# GSM_Relay.net
KiCad netlist of a schematic drawn in EAGLE
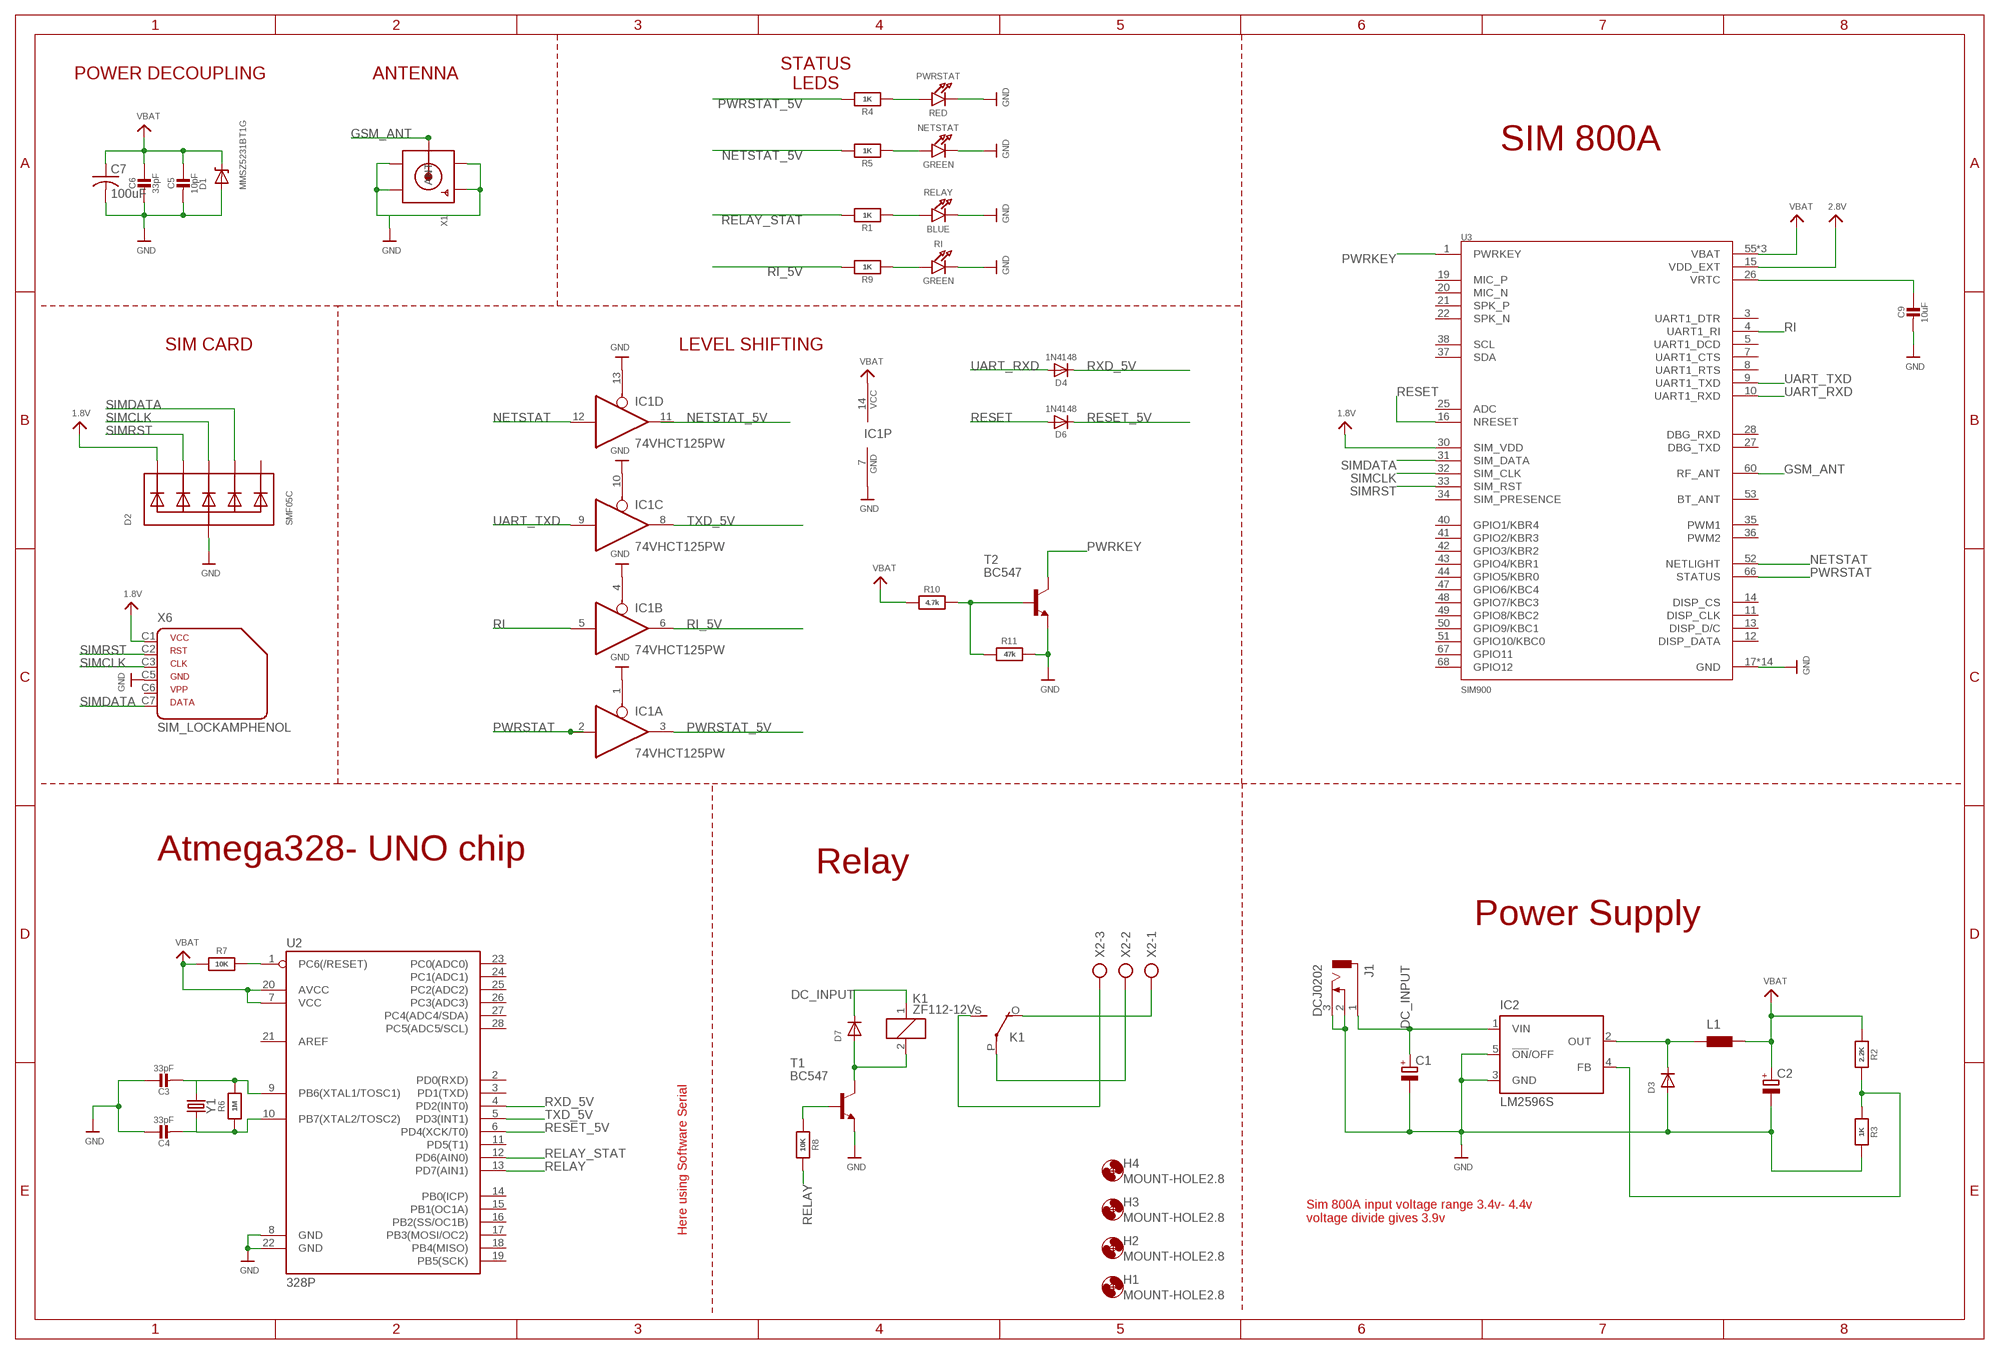
[diagram p0: schematic, sheet 1]

(export (version "E")
  (design (tool "Eeschema 10.0.6"))
  (components
    (comp (ref "C1")
      (value "CPOL-EUE")
      (footprint "eagle-import:PANASONIC_E")
      (libsource (lib "eagle-import") (part "CPOL-EUE"))
    )
    (comp (ref "C2")
      (value "CPOL-EUE")
      (footprint "eagle-import:PANASONIC_E")
      (libsource (lib "eagle-import") (part "CPOL-EUE"))
    )
    (comp (ref "C3")
      (value "33pF")
      (footprint "eagle-import:0805-NO")
      (libsource (lib "eagle-import") (part "CAP_CERAMIC0805-NOOUTLINE"))
    )
    (comp (ref "C4")
      (value "33pF")
      (footprint "eagle-import:0805-NO")
      (libsource (lib "eagle-import") (part "CAP_CERAMIC0805-NOOUTLINE"))
    )
    (comp (ref "C5")
      (value "10pF")
      (footprint "eagle-import:0805-NO")
      (libsource (lib "eagle-import") (part "CAP_CERAMIC0805-NOOUTLINE"))
    )
    (comp (ref "C6")
      (value "33pF")
      (footprint "eagle-import:0805-NO")
      (libsource (lib "eagle-import") (part "CAP_CERAMIC0805-NOOUTLINE"))
    )
    (comp (ref "C7")
      (value "100uF")
      (footprint "eagle-import:C1210")
      (libsource (lib "eagle-import") (part "C-USC1210"))
    )
    (comp (ref "C9")
      (value "10uF")
      (footprint "eagle-import:0805-NO")
      (libsource (lib "eagle-import") (part "CAP_CERAMIC0805-NOOUTLINE"))
    )
    (comp (ref "D1")
      (value "MMSZ5231BT1G")
      (footprint "eagle-import:SOD-123")
      (libsource (lib "eagle-import") (part "DIODE-ZENERSOD123"))
    )
    (comp (ref "D2")
      (value "SMF05C")
      (footprint "eagle-import:SOT363")
      (libsource (lib "eagle-import") (part "TVSARRAY_5LANE"))
    )
    (comp (ref "D3")
      (value "DIODESMA")
      (footprint "eagle-import:SMADIODE")
      (libsource (lib "eagle-import") (part "DIODESMA"))
    )
    (comp (ref "D4")
      (value "1N4148")
      (footprint "eagle-import:SOD-323")
      (libsource (lib "eagle-import") (part "DIODESOD-323"))
    )
    (comp (ref "D6")
      (value "1N4148")
      (footprint "eagle-import:SOD-323")
      (libsource (lib "eagle-import") (part "DIODESOD-323"))
    )
    (comp (ref "D7")
      (value "DIODESMA")
      (footprint "eagle-import:SMADIODE")
      (libsource (lib "eagle-import") (part "DIODESMA"))
    )
    (comp (ref "H1")
      (value "MOUNT-HOLE2.8")
      (footprint "eagle-import:2,8")
      (libsource (lib "eagle-import") (part "MOUNT-HOLE2.8"))
    )
    (comp (ref "H2")
      (value "MOUNT-HOLE2.8")
      (footprint "eagle-import:2,8")
      (libsource (lib "eagle-import") (part "MOUNT-HOLE2.8"))
    )
    (comp (ref "H3")
      (value "MOUNT-HOLE2.8")
      (footprint "eagle-import:2,8")
      (libsource (lib "eagle-import") (part "MOUNT-HOLE2.8"))
    )
    (comp (ref "H4")
      (value "MOUNT-HOLE2.8")
      (footprint "eagle-import:2,8")
      (libsource (lib "eagle-import") (part "MOUNT-HOLE2.8"))
    )
    (comp (ref "IC1")
      (value "74VHCT125PW")
      (footprint "eagle-import:TSSOP14")
      (libsource (lib "eagle-import") (part "74125PWABT"))
    )
    (comp (ref "IC2")
      (value "LM2596S")
      (footprint "eagle-import:TO263-5")
      (fields (field (name "MF") "NATIONAL SEMICONDUCTOR") (field (name "MPN") "LM2596S-ADJ/NOPB"))
      (libsource (lib "eagle-import") (part "LM2596S"))
    )
    (comp (ref "J1")
      (value "DCJ0202")
      (footprint "eagle-import:DCJ0202")
      (libsource (lib "eagle-import") (part "DCJ0202"))
    )
    (comp (ref "K1")
      (value "ZF112-12V")
      (footprint "eagle-import:ZF112")
      (libsource (lib "eagle-import") (part "ZF112"))
    )
    (comp (ref "L1")
      (value "PIS4720")
      (footprint "eagle-import:PIS4720")
      (libsource (lib "eagle-import") (part "PIS4720"))
    )
    (comp (ref "NETSTAT")
      (value "GREEN")
      (footprint "eagle-import:CHIPLED_0805_NOOUTLINE")
      (libsource (lib "eagle-import") (part "LED0805_NOOUTLINE"))
    )
    (comp (ref "PWRSTAT")
      (value "RED")
      (footprint "eagle-import:CHIPLED_0805_NOOUTLINE")
      (libsource (lib "eagle-import") (part "LED0805_NOOUTLINE"))
    )
    (comp (ref "R1")
      (value "1K")
      (footprint "eagle-import:0805-NO")
      (libsource (lib "eagle-import") (part "RESISTOR0805_NOOUTLINE"))
    )
    (comp (ref "R2")
      (value "2.2K")
      (footprint "eagle-import:0805-NO")
      (libsource (lib "eagle-import") (part "RESISTOR0805_NOOUTLINE"))
    )
    (comp (ref "R3")
      (value "1K")
      (footprint "eagle-import:0805-NO")
      (libsource (lib "eagle-import") (part "RESISTOR0805_NOOUTLINE"))
    )
    (comp (ref "R4")
      (value "1K")
      (footprint "eagle-import:0805-NO")
      (libsource (lib "eagle-import") (part "RESISTOR0805_NOOUTLINE"))
    )
    (comp (ref "R5")
      (value "1K")
      (footprint "eagle-import:0805-NO")
      (libsource (lib "eagle-import") (part "RESISTOR0805_NOOUTLINE"))
    )
    (comp (ref "R6")
      (value "1M")
      (footprint "eagle-import:0805-NO")
      (libsource (lib "eagle-import") (part "RESISTOR0805_NOOUTLINE"))
    )
    (comp (ref "R7")
      (value "10K")
      (footprint "eagle-import:0805-NO")
      (libsource (lib "eagle-import") (part "RESISTOR0805_NOOUTLINE"))
    )
    (comp (ref "R8")
      (value "10K")
      (footprint "eagle-import:0805-NO")
      (libsource (lib "eagle-import") (part "RESISTOR0805_NOOUTLINE"))
    )
    (comp (ref "R9")
      (value "1K")
      (footprint "eagle-import:0805-NO")
      (libsource (lib "eagle-import") (part "RESISTOR0805_NOOUTLINE"))
    )
    (comp (ref "R10")
      (value "4.7k")
      (footprint "eagle-import:0805-NO")
      (libsource (lib "eagle-import") (part "RESISTOR0805_NOOUTLINE"))
    )
    (comp (ref "R11")
      (value "47k")
      (footprint "eagle-import:0805-NO")
      (libsource (lib "eagle-import") (part "RESISTOR0805_NOOUTLINE"))
    )
    (comp (ref "RELAY")
      (value "BLUE")
      (footprint "eagle-import:CHIPLED_0805_NOOUTLINE")
      (libsource (lib "eagle-import") (part "LED0805_NOOUTLINE"))
    )
    (comp (ref "RI")
      (value "GREEN")
      (footprint "eagle-import:CHIPLED_0805_NOOUTLINE")
      (libsource (lib "eagle-import") (part "LED0805_NOOUTLINE"))
    )
    (comp (ref "T1")
      (value "BC547")
      (footprint "eagle-import:TO92-EBC-OVAL")
      (libsource (lib "eagle-import") (part "2N2222"))
    )
    (comp (ref "T2")
      (value "BC547")
      (footprint "eagle-import:TO92-EBC-OVAL")
      (libsource (lib "eagle-import") (part "2N2222"))
    )
    (comp (ref "U2")
      (value "328P")
      (footprint "eagle-import:DIP28")
      (libsource (lib "eagle-import") (part "ATMEGA328P_PDIP"))
    )
    (comp (ref "U3")
      (value "SIM900")
      (footprint "eagle-import:QFN100P2400X2400X300-68N")
      (fields (field (name "MF") "Simcom"))
      (libsource (lib "eagle-import") (part "SIM900"))
    )
    (comp (ref "X1")
      (value "SMACONNECTOR")
      (footprint "eagle-import:SMA90_DIP")
      (libsource (lib "eagle-import") (part "SMACONNECTOR"))
    )
    (comp (ref "X2")
      (value "AK300/3")
      (footprint "eagle-import:AK300_3")
      (libsource (lib "eagle-import") (part "AK300/3"))
    )
    (comp (ref "X6")
      (value "SIM_LOCKAMPHENOL")
      (footprint "eagle-import:C707_10M006_512_2")
      (libsource (lib "eagle-import") (part "SIM_LOCKAMPHENOL"))
    )
    (comp (ref "Y1")
      (value "CRYSTALPTH-HC49UV")
      (footprint "eagle-import:HC49U")
      (libsource (lib "eagle-import") (part "CRYSTALPTH-HC49UV"))
    )
  )
  (nets
    (net (code "1") (name "/GSM_ANT") (class "Default")
      (node (ref "U3") (pin "60") (pinfunction "RF_ANT_60") (pintype "bidirectional"))
      (node (ref "X1") (pin "ANTENNA") (pinfunction "ANT_ANTENNA") (pintype "bidirectional"))
    )
    (net (code "2") (name "/NETSTAT") (class "Default")
      (node (ref "IC1") (pin "12") (pinfunction "I_12") (pintype "input"))
      (node (ref "U3") (pin "52") (pinfunction "NETLIGHT_52") (pintype "output"))
    )
    (net (code "3") (name "/NETSTAT_5V") (class "Default")
      (node (ref "IC1") (pin "11") (pinfunction "O_11") (pintype "tri_state"))
      (node (ref "R5") (pin "2") (pinfunction "2_2") (pintype "passive"))
    )
    (net (code "4") (name "/PWRKEY") (class "Default")
      (node (ref "T2") (pin "C") (pinfunction "C_C") (pintype "passive"))
      (node (ref "U3") (pin "1") (pinfunction "PWRKEY_1") (pintype "input"))
    )
    (net (code "5") (name "/PWRSTAT") (class "Default")
      (node (ref "IC1") (pin "2") (pinfunction "I_2") (pintype "input"))
      (node (ref "U3") (pin "66") (pinfunction "STATUS_66") (pintype "output"))
    )
    (net (code "6") (name "/PWRSTAT_5V") (class "Default")
      (node (ref "IC1") (pin "3") (pinfunction "O_3") (pintype "tri_state"))
      (node (ref "R4") (pin "2") (pinfunction "2_2") (pintype "passive"))
    )
    (net (code "7") (name "/RESET") (class "Default")
      (node (ref "D6") (pin "A") (pinfunction "A_A") (pintype "passive"))
      (node (ref "U3") (pin "16") (pinfunction "NRESET_16") (pintype "input"))
    )
    (net (code "8") (name "/RI") (class "Default")
      (node (ref "IC1") (pin "5") (pinfunction "I_5") (pintype "input"))
      (node (ref "U3") (pin "4") (pinfunction "UART1_RI_4") (pintype "input"))
    )
    (net (code "9") (name "/RI_5V") (class "Default")
      (node (ref "IC1") (pin "6") (pinfunction "O_6") (pintype "tri_state"))
      (node (ref "R9") (pin "2") (pinfunction "2_2") (pintype "passive"))
    )
    (net (code "10") (name "/SIMCLK") (class "Default")
      (node (ref "D2") (pin "4") (pinfunction "C3_4") (pintype "passive"))
      (node (ref "U3") (pin "32") (pinfunction "SIM_CLK_32") (pintype "output"))
      (node (ref "X6") (pin "C3") (pinfunction "3_C3") (pintype "passive"))
    )
    (net (code "11") (name "/SIMDATA") (class "Default")
      (node (ref "D2") (pin "5") (pinfunction "C4_5") (pintype "passive"))
      (node (ref "U3") (pin "31") (pinfunction "SIM_DATA_31") (pintype "bidirectional"))
      (node (ref "X6") (pin "C7") (pinfunction "6_C7") (pintype "passive"))
    )
    (net (code "12") (name "/SIMRST") (class "Default")
      (node (ref "D2") (pin "3") (pinfunction "C2_3") (pintype "passive"))
      (node (ref "U3") (pin "33") (pinfunction "SIM_RST_33") (pintype "output"))
      (node (ref "X6") (pin "C2") (pinfunction "2_C2") (pintype "passive"))
    )
    (net (code "13") (name "/UART_RXD") (class "Default")
      (node (ref "D4") (pin "A") (pinfunction "A_A") (pintype "passive"))
      (node (ref "U3") (pin "10") (pinfunction "UART1_RXD_10") (pintype "input"))
    )
    (net (code "14") (name "/UART_TXD") (class "Default")
      (node (ref "IC1") (pin "9") (pinfunction "I_9") (pintype "input"))
      (node (ref "U3") (pin "9") (pinfunction "UART1_TXD_9") (pintype "output"))
    )
    (net (code "15") (name "1.8V") (class "Default")
      (node (ref "D2") (pin "1") (pinfunction "C1_1") (pintype "passive"))
      (node (ref "U3") (pin "30") (pinfunction "SIM_VDD_30") (pintype "output"))
      (node (ref "X6") (pin "C1") (pinfunction "1_C1") (pintype "passive"))
    )
    (net (code "16") (name "2.8V") (class "Default")
      (node (ref "U3") (pin "15") (pinfunction "VDD_EXT_15") (pintype "power_in"))
    )
    (net (code "17") (name "DC_INPUT") (class "Default")
      (node (ref "C1") (pin "+") (pinfunction "+_+") (pintype "passive"))
      (node (ref "D7") (pin "C") (pinfunction "C_C") (pintype "passive"))
      (node (ref "IC2") (pin "1") (pinfunction "VIN_1") (pintype "input"))
      (node (ref "J1") (pin "1") (pinfunction "1_1") (pintype "passive"))
      (node (ref "K1") (pin "1") (pinfunction "1_1") (pintype "passive"))
    )
    (net (code "18") (name "GND") (class "Default")
      (node (ref "C1") (pin "-") (pinfunction "-_-") (pintype "passive"))
      (node (ref "C2") (pin "-") (pinfunction "-_-") (pintype "passive"))
      (node (ref "C3") (pin "1") (pinfunction "1_1") (pintype "passive"))
      (node (ref "C4") (pin "1") (pinfunction "1_1") (pintype "passive"))
      (node (ref "C5") (pin "2") (pinfunction "2_2") (pintype "passive"))
      (node (ref "C6") (pin "2") (pinfunction "2_2") (pintype "passive"))
      (node (ref "C7") (pin "2") (pinfunction "2_2") (pintype "passive"))
      (node (ref "C9") (pin "2") (pinfunction "2_2") (pintype "passive"))
      (node (ref "D1") (pin "A") (pinfunction "A_A") (pintype "passive"))
      (node (ref "D2") (pin "2") (pinfunction "A_2") (pintype "passive"))
      (node (ref "D3") (pin "A") (pinfunction "A_A") (pintype "passive"))
      (node (ref "IC1") (pin "1") (pinfunction "OE_1") (pintype "input"))
      (node (ref "IC1") (pin "10") (pinfunction "OE_10") (pintype "input"))
      (node (ref "IC1") (pin "13") (pinfunction "OE_13") (pintype "input"))
      (node (ref "IC1") (pin "4") (pinfunction "OE_4") (pintype "input"))
      (node (ref "IC1") (pin "7") (pinfunction "GND_7") (pintype "power_in"))
      (node (ref "IC2") (pin "3") (pinfunction "GND_3") (pintype "power_in"))
      (node (ref "IC2") (pin "5") (pinfunction "~{ON}/OFF_5") (pintype "input"))
      (node (ref "J1") (pin "2") (pinfunction "2_2") (pintype "passive"))
      (node (ref "J1") (pin "3") (pinfunction "3_3") (pintype "passive"))
      (node (ref "NETSTAT") (pin "C") (pinfunction "C_C") (pintype "passive"))
      (node (ref "PWRSTAT") (pin "C") (pinfunction "C_C") (pintype "passive"))
      (node (ref "R11") (pin "2") (pinfunction "2_2") (pintype "passive"))
      (node (ref "R3") (pin "2") (pinfunction "2_2") (pintype "passive"))
      (node (ref "RELAY") (pin "C") (pinfunction "C_C") (pintype "passive"))
      (node (ref "RI") (pin "C") (pinfunction "C_C") (pintype "passive"))
      (node (ref "T1") (pin "E") (pinfunction "E_E") (pintype "passive"))
      (node (ref "T2") (pin "E") (pinfunction "E_E") (pintype "passive"))
      (node (ref "U2") (pin "22") (pinfunction "GND_22") (pintype "bidirectional"))
      (node (ref "U2") (pin "8") (pinfunction "GND_8") (pintype "bidirectional"))
      (node (ref "U3") (pin "17") (pinfunction "GND_17") (pintype "power_in"))
      (node (ref "U3") (pin "18") (pinfunction "GND_18") (pintype "power_in"))
      (node (ref "U3") (pin "29") (pinfunction "GND_29") (pintype "power_in"))
      (node (ref "U3") (pin "39") (pinfunction "GND_39") (pintype "power_in"))
      (node (ref "U3") (pin "45") (pinfunction "GND_45") (pintype "power_in"))
      (node (ref "U3") (pin "46") (pinfunction "GND_46") (pintype "power_in"))
      (node (ref "U3") (pin "54") (pinfunction "GND_54") (pintype "power_in"))
      (node (ref "U3") (pin "58") (pinfunction "GND_58") (pintype "power_in"))
      (node (ref "U3") (pin "59") (pinfunction "GND_59") (pintype "power_in"))
      (node (ref "U3") (pin "61") (pinfunction "GND_61") (pintype "power_in"))
      (node (ref "U3") (pin "62") (pinfunction "GND_62") (pintype "power_in"))
      (node (ref "U3") (pin "63") (pinfunction "GND_63") (pintype "power_in"))
      (node (ref "U3") (pin "64") (pinfunction "GND_64") (pintype "power_in"))
      (node (ref "U3") (pin "65") (pinfunction "GND_65") (pintype "power_in"))
      (node (ref "X1") (pin "GND1") (pinfunction "GND1_GND1") (pintype "power_in"))
      (node (ref "X1") (pin "GND2") (pinfunction "GND2_GND2") (pintype "power_in"))
      (node (ref "X1") (pin "GND3") (pinfunction "GND3_GND3") (pintype "power_in"))
      (node (ref "X1") (pin "GND4") (pinfunction "GND4_GND4") (pintype "power_in"))
      (node (ref "X6") (pin "C5") (pinfunction "4_C5") (pintype "passive"))
    )
    (net (code "19") (name "Net-(D7-PadA)") (class "Default")
      (node (ref "D7") (pin "A") (pinfunction "A_A") (pintype "passive"))
      (node (ref "K1") (pin "2") (pinfunction "2_2") (pintype "passive"))
      (node (ref "T1") (pin "C") (pinfunction "C_C") (pintype "passive"))
    )
    (net (code "20") (name "Net-(IC2-FB)") (class "Default")
      (node (ref "IC2") (pin "4") (pinfunction "FB_4") (pintype "input"))
      (node (ref "R2") (pin "2") (pinfunction "2_2") (pintype "passive"))
      (node (ref "R3") (pin "1") (pinfunction "1_1") (pintype "passive"))
    )
    (net (code "21") (name "Net-(IC2-OUT)") (class "Default")
      (node (ref "D3") (pin "C") (pinfunction "C_C") (pintype "passive"))
      (node (ref "IC2") (pin "2") (pinfunction "OUT_2") (pintype "output"))
      (node (ref "L1") (pin "P$1") (pinfunction "P$1_P$1") (pintype "bidirectional"))
    )
    (net (code "22") (name "Net-(NETSTAT-PadA)") (class "Default")
      (node (ref "NETSTAT") (pin "A") (pinfunction "A_A") (pintype "passive"))
      (node (ref "R5") (pin "1") (pinfunction "1_1") (pintype "passive"))
    )
    (net (code "23") (name "Net-(PWRSTAT-PadA)") (class "Default")
      (node (ref "PWRSTAT") (pin "A") (pinfunction "A_A") (pintype "passive"))
      (node (ref "R4") (pin "1") (pinfunction "1_1") (pintype "passive"))
    )
    (net (code "24") (name "Net-(R1-Pad1)") (class "Default")
      (node (ref "R1") (pin "1") (pinfunction "1_1") (pintype "passive"))
      (node (ref "RELAY") (pin "A") (pinfunction "A_A") (pintype "passive"))
    )
    (net (code "25") (name "Net-(R8-Pad1)") (class "Default")
      (node (ref "R8") (pin "1") (pinfunction "1_1") (pintype "passive"))
      (node (ref "T1") (pin "B") (pinfunction "B_B") (pintype "passive"))
    )
    (net (code "26") (name "Net-(R9-Pad1)") (class "Default")
      (node (ref "R9") (pin "1") (pinfunction "1_1") (pintype "passive"))
      (node (ref "RI") (pin "A") (pinfunction "A_A") (pintype "passive"))
    )
    (net (code "27") (name "Net-(R10-Pad2)") (class "Default")
      (node (ref "R10") (pin "2") (pinfunction "2_2") (pintype "passive"))
      (node (ref "R11") (pin "1") (pinfunction "1_1") (pintype "passive"))
      (node (ref "T2") (pin "B") (pinfunction "B_B") (pintype "passive"))
    )
    (net (code "28") (name "Net-(U2-PB6(XTAL1{slash}TOSC1))") (class "Default")
      (node (ref "C3") (pin "2") (pinfunction "2_2") (pintype "passive"))
      (node (ref "R6") (pin "2") (pinfunction "2_2") (pintype "passive"))
      (node (ref "U2") (pin "9") (pinfunction "PB6(XTAL1/TOSC1)_9") (pintype "bidirectional"))
      (node (ref "Y1") (pin "1") (pinfunction "1_1") (pintype "passive"))
    )
    (net (code "29") (name "Net-(U2-PB7(XTAL2{slash}TOSC2))") (class "Default")
      (node (ref "C4") (pin "2") (pinfunction "2_2") (pintype "passive"))
      (node (ref "R6") (pin "1") (pinfunction "1_1") (pintype "passive"))
      (node (ref "U2") (pin "10") (pinfunction "PB7(XTAL2/TOSC2)_10") (pintype "bidirectional"))
      (node (ref "Y1") (pin "2") (pinfunction "2_2") (pintype "passive"))
    )
    (net (code "30") (name "Net-(U2-PC6({slash}RESET))") (class "Default")
      (node (ref "R7") (pin "2") (pinfunction "2_2") (pintype "passive"))
      (node (ref "U2") (pin "1") (pinfunction "PC6(/RESET)_1") (pintype "bidirectional"))
    )
    (net (code "31") (name "Net-(U3-VRTC)") (class "Default")
      (node (ref "C9") (pin "1") (pinfunction "1_1") (pintype "passive"))
      (node (ref "U3") (pin "26") (pinfunction "VRTC_26") (pintype "power_in"))
    )
    (net (code "32") (name "Net-(X2A-KL)") (class "Default")
      (node (ref "K1") (pin "O") (pinfunction "O_O") (pintype "passive"))
      (node (ref "X2") (pin "1") (pinfunction "KL_1") (pintype "passive"))
    )
    (net (code "33") (name "Net-(X2B-KL)") (class "Default")
      (node (ref "K1") (pin "P") (pinfunction "P_P") (pintype "passive"))
      (node (ref "X2") (pin "2") (pinfunction "KL_2") (pintype "passive"))
    )
    (net (code "34") (name "Net-(X2C-KL)") (class "Default")
      (node (ref "K1") (pin "S") (pinfunction "S_S") (pintype "passive"))
      (node (ref "X2") (pin "3") (pinfunction "KL_3") (pintype "passive"))
    )
    (net (code "35") (name "RELAY") (class "Default")
      (node (ref "R8") (pin "2") (pinfunction "2_2") (pintype "passive"))
      (node (ref "U2") (pin "13") (pinfunction "PD7(AIN1)_13") (pintype "bidirectional"))
    )
    (net (code "36") (name "RELAY_STAT") (class "Default")
      (node (ref "R1") (pin "2") (pinfunction "2_2") (pintype "passive"))
      (node (ref "U2") (pin "12") (pinfunction "PD6(AIN0)_12") (pintype "bidirectional"))
    )
    (net (code "37") (name "RESET_5V") (class "Default")
      (node (ref "D6") (pin "C") (pinfunction "C_C") (pintype "passive"))
      (node (ref "U2") (pin "6") (pinfunction "PD4(XCK/T0)_6") (pintype "bidirectional"))
    )
    (net (code "38") (name "RXD_5V") (class "Default")
      (node (ref "D4") (pin "C") (pinfunction "C_C") (pintype "passive"))
      (node (ref "U2") (pin "4") (pinfunction "PD2(INT0)_4") (pintype "bidirectional"))
    )
    (net (code "39") (name "TXD_5V") (class "Default")
      (node (ref "IC1") (pin "8") (pinfunction "O_8") (pintype "tri_state"))
      (node (ref "U2") (pin "5") (pinfunction "PD3(INT1)_5") (pintype "bidirectional"))
    )
    (net (code "40") (name "VBAT") (class "Default")
      (node (ref "C2") (pin "+") (pinfunction "+_+") (pintype "passive"))
      (node (ref "C5") (pin "1") (pinfunction "1_1") (pintype "passive"))
      (node (ref "C6") (pin "1") (pinfunction "1_1") (pintype "passive"))
      (node (ref "C7") (pin "1") (pinfunction "1_1") (pintype "passive"))
      (node (ref "D1") (pin "C") (pinfunction "C_C") (pintype "passive"))
      (node (ref "IC1") (pin "14") (pinfunction "VCC_14") (pintype "power_in"))
      (node (ref "L1") (pin "P$2") (pinfunction "P$2_P$2") (pintype "bidirectional"))
      (node (ref "R10") (pin "1") (pinfunction "1_1") (pintype "passive"))
      (node (ref "R2") (pin "1") (pinfunction "1_1") (pintype "passive"))
      (node (ref "R7") (pin "1") (pinfunction "1_1") (pintype "passive"))
      (node (ref "U2") (pin "20") (pinfunction "AVCC_20") (pintype "bidirectional"))
      (node (ref "U2") (pin "7") (pinfunction "VCC_7") (pintype "bidirectional"))
      (node (ref "U3") (pin "55") (pinfunction "VBAT_55") (pintype "power_in"))
      (node (ref "U3") (pin "56") (pinfunction "VBAT_56") (pintype "power_in"))
      (node (ref "U3") (pin "57") (pinfunction "VBAT_57") (pintype "power_in"))
    )
    (net (code "41") (name "unconnected-(D2-C5-Pad6)") (class "Default")
      (node (ref "D2") (pin "6") (pinfunction "C5_6") (pintype "passive"))
    )
    (net (code "42") (name "unconnected-(U2-AREF-Pad21)") (class "Default")
      (node (ref "U2") (pin "21") (pinfunction "AREF_21") (pintype "bidirectional"))
    )
    (net (code "43") (name "unconnected-(U2-PB0(ICP)-Pad14)") (class "Default")
      (node (ref "U2") (pin "14") (pinfunction "PB0(ICP)_14") (pintype "bidirectional"))
    )
    (net (code "44") (name "unconnected-(U2-PB1(OC1A)-Pad15)") (class "Default")
      (node (ref "U2") (pin "15") (pinfunction "PB1(OC1A)_15") (pintype "bidirectional"))
    )
    (net (code "45") (name "unconnected-(U2-PB2(SS{slash}OC1B)-Pad16)") (class "Default")
      (node (ref "U2") (pin "16") (pinfunction "PB2(SS/OC1B)_16") (pintype "bidirectional"))
    )
    (net (code "46") (name "unconnected-(U2-PB3(MOSI{slash}OC2)-Pad17)") (class "Default")
      (node (ref "U2") (pin "17") (pinfunction "PB3(MOSI/OC2)_17") (pintype "bidirectional"))
    )
    (net (code "47") (name "unconnected-(U2-PB4(MISO)-Pad18)") (class "Default")
      (node (ref "U2") (pin "18") (pinfunction "PB4(MISO)_18") (pintype "bidirectional"))
    )
    (net (code "48") (name "unconnected-(U2-PB5(SCK)-Pad19)") (class "Default")
      (node (ref "U2") (pin "19") (pinfunction "PB5(SCK)_19") (pintype "bidirectional"))
    )
    (net (code "49") (name "unconnected-(U2-PC0(ADC0)-Pad23)") (class "Default")
      (node (ref "U2") (pin "23") (pinfunction "PC0(ADC0)_23") (pintype "bidirectional"))
    )
    (net (code "50") (name "unconnected-(U2-PC1(ADC1)-Pad24)") (class "Default")
      (node (ref "U2") (pin "24") (pinfunction "PC1(ADC1)_24") (pintype "bidirectional"))
    )
    (net (code "51") (name "unconnected-(U2-PC2(ADC2)-Pad25)") (class "Default")
      (node (ref "U2") (pin "25") (pinfunction "PC2(ADC2)_25") (pintype "bidirectional"))
    )
    (net (code "52") (name "unconnected-(U2-PC3(ADC3)-Pad26)") (class "Default")
      (node (ref "U2") (pin "26") (pinfunction "PC3(ADC3)_26") (pintype "bidirectional"))
    )
    (net (code "53") (name "unconnected-(U2-PC4(ADC4{slash}SDA)-Pad27)") (class "Default")
      (node (ref "U2") (pin "27") (pinfunction "PC4(ADC4/SDA)_27") (pintype "bidirectional"))
    )
    (net (code "54") (name "unconnected-(U2-PC5(ADC5{slash}SCL)-Pad28)") (class "Default")
      (node (ref "U2") (pin "28") (pinfunction "PC5(ADC5/SCL)_28") (pintype "bidirectional"))
    )
    (net (code "55") (name "unconnected-(U2-PD0(RXD)-Pad2)") (class "Default")
      (node (ref "U2") (pin "2") (pinfunction "PD0(RXD)_2") (pintype "bidirectional"))
    )
    (net (code "56") (name "unconnected-(U2-PD1(TXD)-Pad3)") (class "Default")
      (node (ref "U2") (pin "3") (pinfunction "PD1(TXD)_3") (pintype "bidirectional"))
    )
    (net (code "57") (name "unconnected-(U2-PD5(T1)-Pad11)") (class "Default")
      (node (ref "U2") (pin "11") (pinfunction "PD5(T1)_11") (pintype "bidirectional"))
    )
    (net (code "58") (name "unconnected-(U3-ADC-Pad25)") (class "Default")
      (node (ref "U3") (pin "25") (pinfunction "ADC_25") (pintype "input"))
    )
    (net (code "59") (name "unconnected-(U3-BT_ANT-Pad53)") (class "Default")
      (node (ref "U3") (pin "53") (pinfunction "BT_ANT_53") (pintype "bidirectional"))
    )
    (net (code "60") (name "unconnected-(U3-DBG_RXD-Pad28)") (class "Default")
      (node (ref "U3") (pin "28") (pinfunction "DBG_RXD_28") (pintype "input"))
    )
    (net (code "61") (name "unconnected-(U3-DBG_TXD-Pad27)") (class "Default")
      (node (ref "U3") (pin "27") (pinfunction "DBG_TXD_27") (pintype "output"))
    )
    (net (code "62") (name "unconnected-(U3-DISP_CLK-Pad11)") (class "Default")
      (node (ref "U3") (pin "11") (pinfunction "DISP_CLK_11") (pintype "output"))
    )
    (net (code "63") (name "unconnected-(U3-DISP_CS-Pad14)") (class "Default")
      (node (ref "U3") (pin "14") (pinfunction "DISP_CS_14") (pintype "output"))
    )
    (net (code "64") (name "unconnected-(U3-DISP_DATA-Pad12)") (class "Default")
      (node (ref "U3") (pin "12") (pinfunction "DISP_DATA_12") (pintype "bidirectional"))
    )
    (net (code "65") (name "unconnected-(U3-DISP_D{slash}C-Pad13)") (class "Default")
      (node (ref "U3") (pin "13") (pinfunction "DISP_D/C_13") (pintype "output"))
    )
    (net (code "66") (name "unconnected-(U3-GPIO1{slash}KBR4-Pad40)") (class "Default")
      (node (ref "U3") (pin "40") (pinfunction "GPIO1/KBR4_40") (pintype "bidirectional"))
    )
    (net (code "67") (name "unconnected-(U3-GPIO2{slash}KBR3-Pad41)") (class "Default")
      (node (ref "U3") (pin "41") (pinfunction "GPIO2/KBR3_41") (pintype "bidirectional"))
    )
    (net (code "68") (name "unconnected-(U3-GPIO3{slash}KBR2-Pad42)") (class "Default")
      (node (ref "U3") (pin "42") (pinfunction "GPIO3/KBR2_42") (pintype "bidirectional"))
    )
    (net (code "69") (name "unconnected-(U3-GPIO4{slash}KBR1-Pad43)") (class "Default")
      (node (ref "U3") (pin "43") (pinfunction "GPIO4/KBR1_43") (pintype "bidirectional"))
    )
    (net (code "70") (name "unconnected-(U3-GPIO5{slash}KBR0-Pad44)") (class "Default")
      (node (ref "U3") (pin "44") (pinfunction "GPIO5/KBR0_44") (pintype "bidirectional"))
    )
    (net (code "71") (name "unconnected-(U3-GPIO6{slash}KBC4-Pad47)") (class "Default")
      (node (ref "U3") (pin "47") (pinfunction "GPIO6/KBC4_47") (pintype "bidirectional"))
    )
    (net (code "72") (name "unconnected-(U3-GPIO7{slash}KBC3-Pad48)") (class "Default")
      (node (ref "U3") (pin "48") (pinfunction "GPIO7/KBC3_48") (pintype "bidirectional"))
    )
    (net (code "73") (name "unconnected-(U3-GPIO8{slash}KBC2-Pad49)") (class "Default")
      (node (ref "U3") (pin "49") (pinfunction "GPIO8/KBC2_49") (pintype "bidirectional"))
    )
    (net (code "74") (name "unconnected-(U3-GPIO9{slash}KBC1-Pad50)") (class "Default")
      (node (ref "U3") (pin "50") (pinfunction "GPIO9/KBC1_50") (pintype "bidirectional"))
    )
    (net (code "75") (name "unconnected-(U3-GPIO10{slash}KBC0-Pad51)") (class "Default")
      (node (ref "U3") (pin "51") (pinfunction "GPIO10/KBC0_51") (pintype "bidirectional"))
    )
    (net (code "76") (name "unconnected-(U3-GPIO11-Pad67)") (class "Default")
      (node (ref "U3") (pin "67") (pinfunction "GPIO11_67") (pintype "bidirectional"))
    )
    (net (code "77") (name "unconnected-(U3-GPIO12-Pad68)") (class "Default")
      (node (ref "U3") (pin "68") (pinfunction "GPIO12_68") (pintype "bidirectional"))
    )
    (net (code "78") (name "unconnected-(U3-MIC_N-Pad20)") (class "Default")
      (node (ref "U3") (pin "20") (pinfunction "MIC_N_20") (pintype "input"))
    )
    (net (code "79") (name "unconnected-(U3-MIC_P-Pad19)") (class "Default")
      (node (ref "U3") (pin "19") (pinfunction "MIC_P_19") (pintype "input"))
    )
    (net (code "80") (name "unconnected-(U3-PWM1-Pad35)") (class "Default")
      (node (ref "U3") (pin "35") (pinfunction "PWM1_35") (pintype "output"))
    )
    (net (code "81") (name "unconnected-(U3-PWM2-Pad36)") (class "Default")
      (node (ref "U3") (pin "36") (pinfunction "PWM2_36") (pintype "output"))
    )
    (net (code "82") (name "unconnected-(U3-SCL-Pad38)") (class "Default")
      (node (ref "U3") (pin "38") (pinfunction "SCL_38") (pintype "bidirectional"))
    )
    (net (code "83") (name "unconnected-(U3-SDA-Pad37)") (class "Default")
      (node (ref "U3") (pin "37") (pinfunction "SDA_37") (pintype "output"))
    )
    (net (code "84") (name "unconnected-(U3-SIM_PRESENCE-Pad34)") (class "Default")
      (node (ref "U3") (pin "34") (pinfunction "SIM_PRESENCE_34") (pintype "input"))
    )
    (net (code "85") (name "unconnected-(U3-SPK_N-Pad22)") (class "Default")
      (node (ref "U3") (pin "22") (pinfunction "SPK_N_22") (pintype "output"))
    )
    (net (code "86") (name "unconnected-(U3-SPK_P-Pad21)") (class "Default")
      (node (ref "U3") (pin "21") (pinfunction "SPK_P_21") (pintype "output"))
    )
    (net (code "87") (name "unconnected-(U3-UART1_CTS-Pad7)") (class "Default")
      (node (ref "U3") (pin "7") (pinfunction "UART1_CTS_7") (pintype "output"))
    )
    (net (code "88") (name "unconnected-(U3-UART1_DCD-Pad5)") (class "Default")
      (node (ref "U3") (pin "5") (pinfunction "UART1_DCD_5") (pintype "output"))
    )
    (net (code "89") (name "unconnected-(U3-UART1_DTR-Pad3)") (class "Default")
      (node (ref "U3") (pin "3") (pinfunction "UART1_DTR_3") (pintype "input"))
    )
    (net (code "90") (name "unconnected-(U3-UART1_RTS-Pad8)") (class "Default")
      (node (ref "U3") (pin "8") (pinfunction "UART1_RTS_8") (pintype "input"))
    )
    (net (code "91") (name "unconnected-(X6-5-PadC6)") (class "Default")
      (node (ref "X6") (pin "C6") (pinfunction "5_C6") (pintype "passive"))
    )
  )
)
